# PIC32.net
KiCad netlist of a schematic drawn in Altium Designer
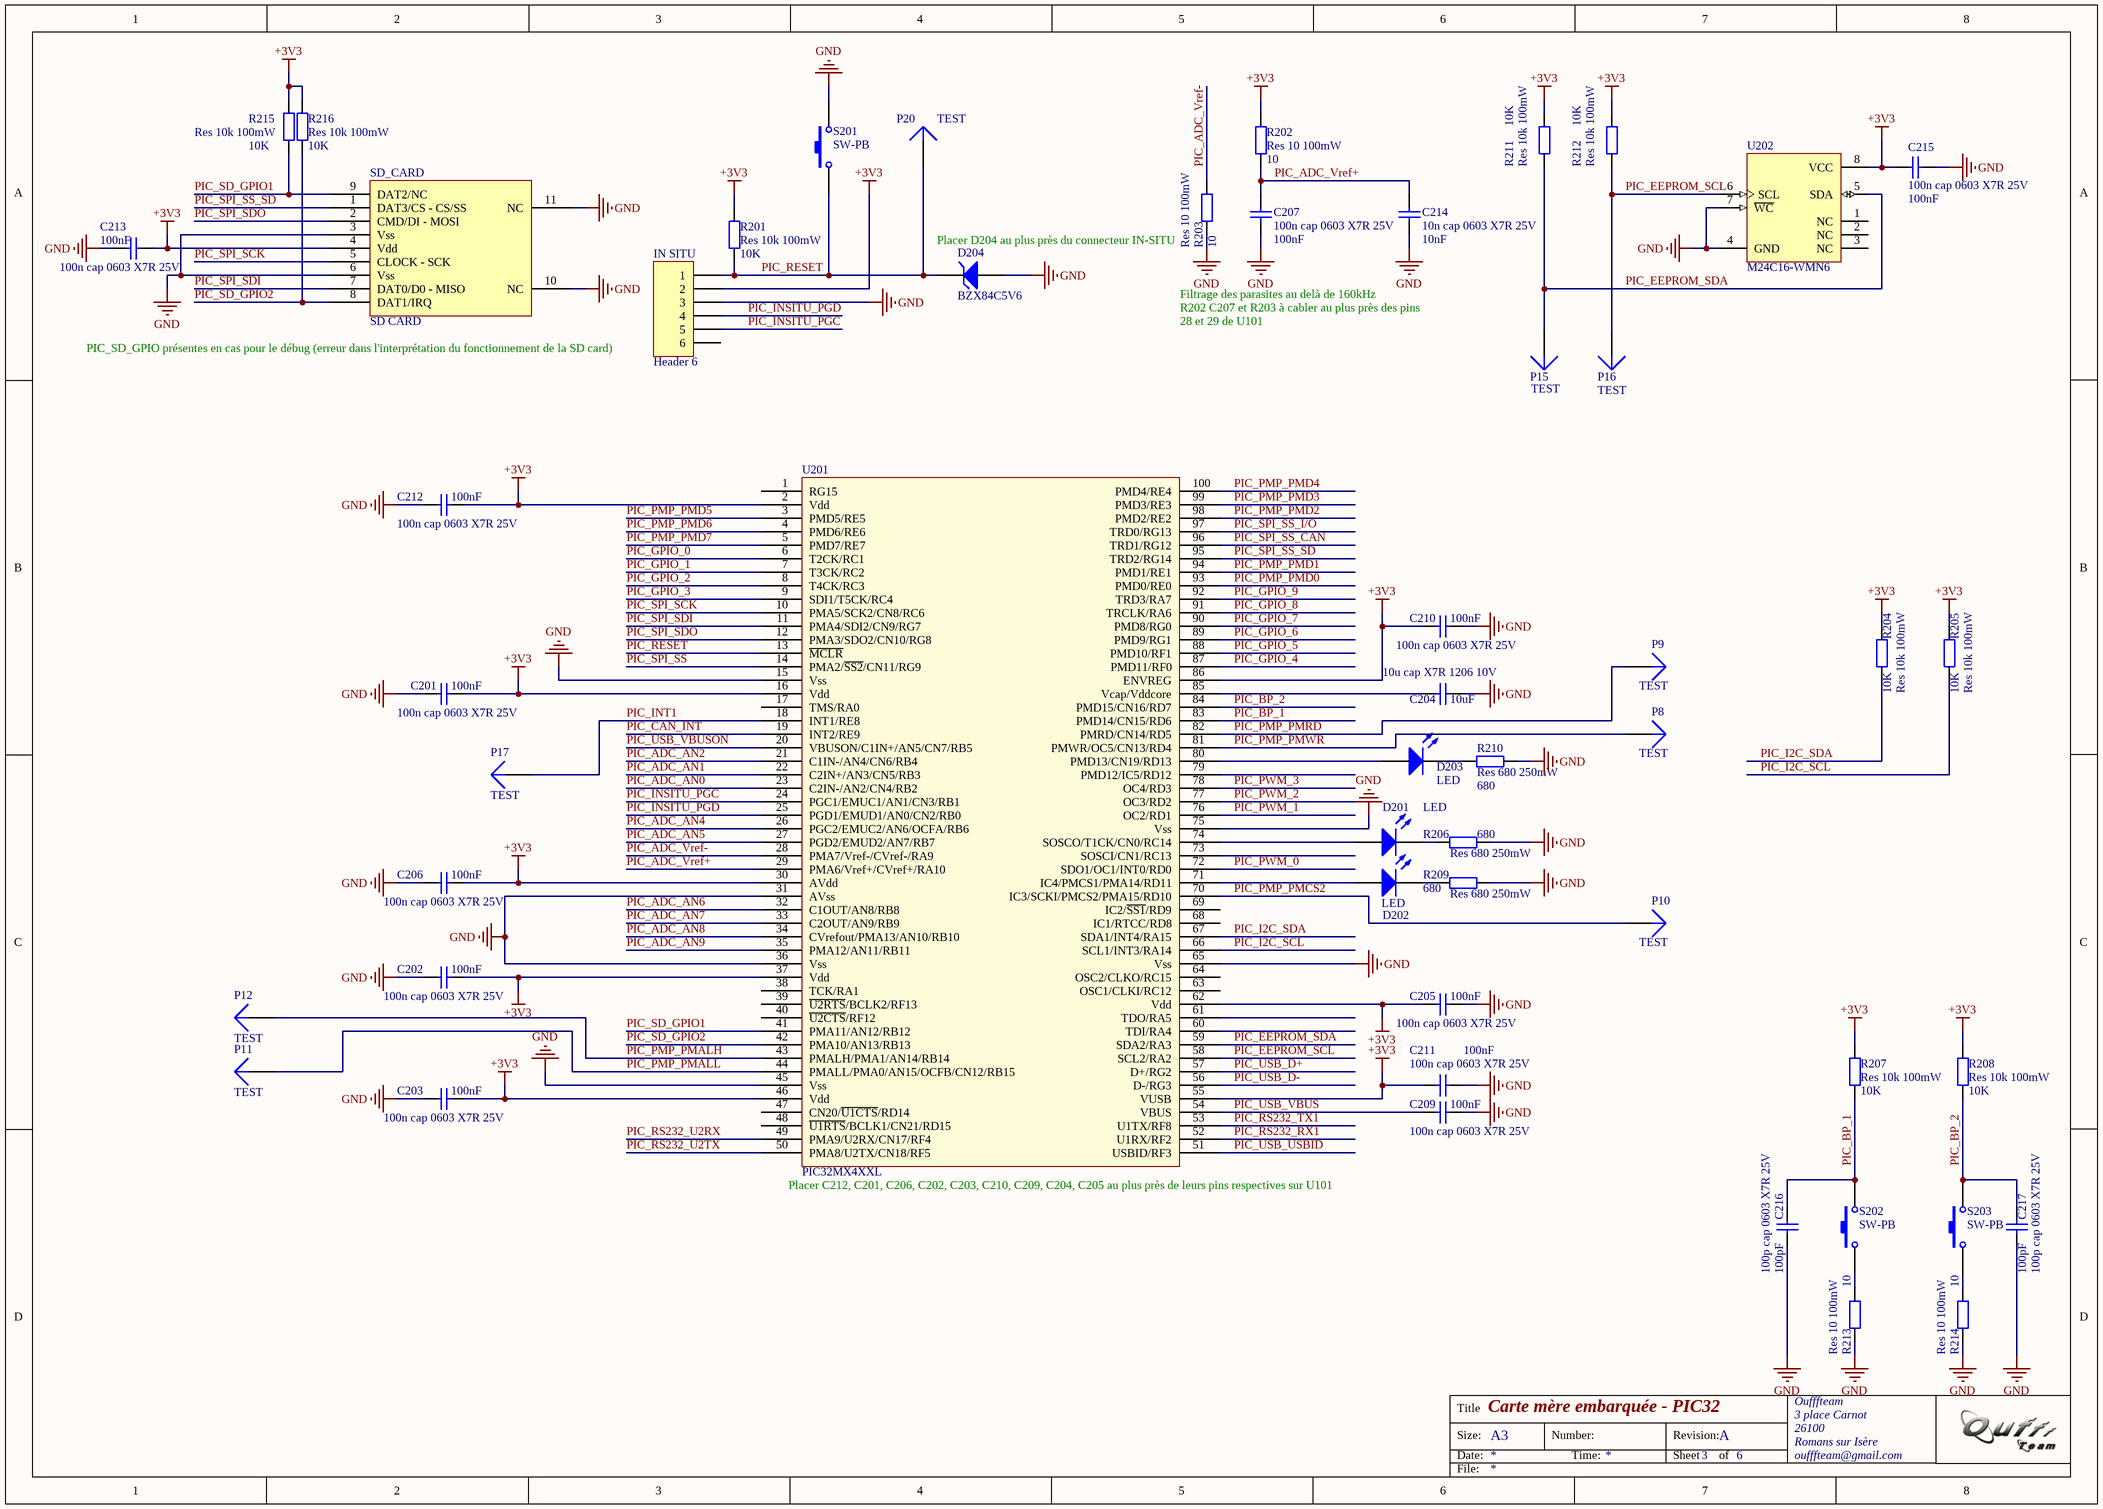
[diagram p0: PIC32.SchDoc]

(export (version "E")
  (design (tool "Eeschema 10.0.6"))
  (components
    (comp (ref "C201")
      (value "100n cap 0603 X7R 25V")
      (footprint "1608[0603]")
      (description "Capacitor")
      (fields (field (name "ALTIUM_VALUE") "100nF") (field (name "PUBLISHER") "Altium Limited"))
      (libsource (lib "Miscellaneous Devices") (part "Cap"))
    )
    (comp (ref "C202")
      (value "100n cap 0603 X7R 25V")
      (footprint "1608[0603]")
      (description "Capacitor")
      (fields (field (name "ALTIUM_VALUE") "100nF") (field (name "PUBLISHER") "Altium Limited"))
      (libsource (lib "Miscellaneous Devices") (part "Cap"))
    )
    (comp (ref "C203")
      (value "100n cap 0603 X7R 25V")
      (footprint "1608[0603]")
      (description "Capacitor")
      (fields (field (name "ALTIUM_VALUE") "100nF") (field (name "PUBLISHER") "Altium Limited"))
      (libsource (lib "Miscellaneous Devices") (part "Cap"))
    )
    (comp (ref "C204")
      (value "10u cap X7R 1206 10V")
      (footprint "3216[1206]")
      (description "Capacitor")
      (fields (field (name "ALTIUM_VALUE") "10uF") (field (name "PUBLISHER") "Altium Limited"))
      (libsource (lib "Miscellaneous Devices") (part "Cap"))
    )
    (comp (ref "C205")
      (value "100n cap 0603 X7R 25V")
      (footprint "1608[0603]")
      (description "Capacitor")
      (fields (field (name "ALTIUM_VALUE") "100nF") (field (name "PUBLISHER") "Altium Limited"))
      (libsource (lib "Miscellaneous Devices") (part "Cap"))
    )
    (comp (ref "C206")
      (value "100n cap 0603 X7R 25V")
      (footprint "1608[0603]")
      (description "Capacitor")
      (fields (field (name "ALTIUM_VALUE") "100nF") (field (name "PUBLISHER") "Altium Limited"))
      (libsource (lib "Miscellaneous Devices") (part "Cap"))
    )
    (comp (ref "C207")
      (value "100n cap 0603 X7R 25V")
      (footprint "1608[0603]")
      (description "Capacitor")
      (fields (field (name "ALTIUM_VALUE") "100nF") (field (name "PUBLISHER") "Altium Limited"))
      (libsource (lib "Miscellaneous Devices") (part "Cap"))
    )
    (comp (ref "C209")
      (value "100n cap 0603 X7R 25V")
      (footprint "1608[0603]")
      (description "Capacitor")
      (fields (field (name "ALTIUM_VALUE") "100nF") (field (name "PUBLISHER") "Altium Limited"))
      (libsource (lib "Miscellaneous Devices") (part "Cap"))
    )
    (comp (ref "C210")
      (value "100n cap 0603 X7R 25V")
      (footprint "1608[0603]")
      (description "Capacitor")
      (fields (field (name "ALTIUM_VALUE") "100nF") (field (name "PUBLISHER") "Altium Limited"))
      (libsource (lib "Miscellaneous Devices") (part "Cap"))
    )
    (comp (ref "C211")
      (value "100n cap 0603 X7R 25V")
      (footprint "1608[0603]")
      (description "Capacitor")
      (fields (field (name "ALTIUM_VALUE") "100nF") (field (name "PUBLISHER") "Altium Limited"))
      (libsource (lib "Miscellaneous Devices") (part "Cap"))
    )
    (comp (ref "C212")
      (value "100n cap 0603 X7R 25V")
      (footprint "1608[0603]")
      (description "Capacitor")
      (fields (field (name "ALTIUM_VALUE") "100nF") (field (name "PUBLISHER") "Altium Limited"))
      (libsource (lib "Miscellaneous Devices") (part "Cap"))
    )
    (comp (ref "C213")
      (value "100n cap 0603 X7R 25V")
      (footprint "1608[0603]")
      (description "Capacitor")
      (fields (field (name "ALTIUM_VALUE") "100nF") (field (name "PUBLISHER") "Altium Limited"))
      (libsource (lib "Miscellaneous Devices") (part "Cap"))
    )
    (comp (ref "C214")
      (value "10n cap 0603 X7R 25V")
      (footprint "1608[0603]")
      (description "Capacitor")
      (fields (field (name "ALTIUM_VALUE") "10nF") (field (name "PUBLISHER") "Altium Limited"))
      (libsource (lib "Miscellaneous Devices") (part "Cap"))
    )
    (comp (ref "C215")
      (value "100n cap 0603 X7R 25V")
      (footprint "1608[0603]")
      (description "Capacitor")
      (fields (field (name "ALTIUM_VALUE") "100nF") (field (name "PUBLISHER") "Altium Limited"))
      (libsource (lib "Miscellaneous Devices") (part "Cap"))
    )
    (comp (ref "C216")
      (value "100p cap 0603 X7R 25V")
      (footprint "1608[0603]")
      (description "Capacitor")
      (fields (field (name "ALTIUM_VALUE") "100pF") (field (name "PUBLISHER") "Altium Limited"))
      (libsource (lib "Miscellaneous Devices") (part "Cap"))
    )
    (comp (ref "C217")
      (value "100p cap 0603 X7R 25V")
      (footprint "1608[0603]")
      (description "Capacitor")
      (fields (field (name "ALTIUM_VALUE") "100pF") (field (name "PUBLISHER") "Altium Limited"))
      (libsource (lib "Miscellaneous Devices") (part "Cap"))
    )
    (comp (ref "D201")
      (value "LED")
      (footprint "1608[0603]")
      (description "LED SML-311DTT86")
      (fields (field (name "PUBLISHER") "Altium Limited"))
      (libsource (lib "Miscellaneous Devices") (part "LED0"))
    )
    (comp (ref "D202")
      (value "LED")
      (footprint "1608[0603]")
      (description "LED SML-311DTT86")
      (fields (field (name "PUBLISHER") "Altium Limited"))
      (libsource (lib "Miscellaneous Devices") (part "LED0"))
    )
    (comp (ref "D203")
      (value "LED")
      (footprint "1608[0603]")
      (description "LED SML-311DTT86")
      (fields (field (name "PUBLISHER") "Altium Limited"))
      (libsource (lib "Miscellaneous Devices") (part "LED0"))
    )
    (comp (ref "D204")
      (value "BZX84C5V6")
      (footprint "318-07")
      (description "Zener Voltage Regulator Diode")
      (fields (field (name "PUBLISHER") "Altium Limited"))
      (libsource (lib "Motorola Discrete Diode") (part "BZX84C5V6LT1"))
    )
    (comp (ref "IN SITU")
      (value "Header 6")
      (footprint "HDR1X6")
      (description "Header, 6-Pin")
      (fields (field (name "PUBLISHER") "Altium Limited"))
      (libsource (lib "Miscellaneous Connectors") (part "Header 6"))
    )
    (comp (ref "P8")
      (value "TEST")
      (footprint "TP1")
      (description "Plug")
      (fields (field (name "PUBLISHER") "Altium Limited"))
      (libsource (lib "Miscellaneous Connectors") (part "Plug"))
    )
    (comp (ref "P9")
      (value "TEST")
      (footprint "TP1")
      (description "Plug")
      (fields (field (name "PUBLISHER") "Altium Limited"))
      (libsource (lib "Miscellaneous Connectors") (part "Plug"))
    )
    (comp (ref "P10")
      (value "TEST")
      (footprint "TP1")
      (description "Plug")
      (fields (field (name "PUBLISHER") "Altium Limited"))
      (libsource (lib "Miscellaneous Connectors") (part "Plug"))
    )
    (comp (ref "P11")
      (value "TEST")
      (footprint "TP1")
      (description "Plug")
      (fields (field (name "PUBLISHER") "Altium Limited"))
      (libsource (lib "Miscellaneous Connectors") (part "Plug"))
    )
    (comp (ref "P12")
      (value "TEST")
      (footprint "TP1")
      (description "Plug")
      (fields (field (name "PUBLISHER") "Altium Limited"))
      (libsource (lib "Miscellaneous Connectors") (part "Plug"))
    )
    (comp (ref "P15")
      (value "TEST")
      (footprint "TP1")
      (description "Plug")
      (fields (field (name "PUBLISHER") "Altium Limited"))
      (libsource (lib "Miscellaneous Connectors") (part "Plug"))
    )
    (comp (ref "P16")
      (value "TEST")
      (footprint "TP1")
      (description "Plug")
      (fields (field (name "PUBLISHER") "Altium Limited"))
      (libsource (lib "Miscellaneous Connectors") (part "Plug"))
    )
    (comp (ref "P17")
      (value "TEST")
      (footprint "TP1")
      (description "Plug")
      (fields (field (name "PUBLISHER") "Altium Limited"))
      (libsource (lib "Miscellaneous Connectors") (part "Plug"))
    )
    (comp (ref "P20")
      (value "TEST")
      (footprint "TP1")
      (description "Plug")
      (fields (field (name "PUBLISHER") "Altium Limited"))
      (libsource (lib "Miscellaneous Connectors") (part "Plug"))
    )
    (comp (ref "R201")
      (value "Res 10k 100mW")
      (footprint "1608[0603]")
      (description "Resistor")
      (fields (field (name "ALTIUM_VALUE") "10K") (field (name "PUBLISHER") "Altium Limited"))
      (libsource (lib "Miscellaneous Devices") (part "Res2"))
    )
    (comp (ref "R202")
      (value "Res 10 100mW")
      (footprint "1608[0603]")
      (description "Resistor")
      (fields (field (name "ALTIUM_VALUE") "10") (field (name "PUBLISHER") "Altium Limited"))
      (libsource (lib "Miscellaneous Devices") (part "Res2"))
    )
    (comp (ref "R203")
      (value "Res 10 100mW")
      (footprint "1608[0603]")
      (description "Resistor")
      (fields (field (name "ALTIUM_VALUE") "10") (field (name "PUBLISHER") "Altium Limited"))
      (libsource (lib "Miscellaneous Devices") (part "Res2"))
    )
    (comp (ref "R204")
      (value "Res 10k 100mW")
      (footprint "1608[0603]")
      (description "Resistor")
      (fields (field (name "ALTIUM_VALUE") "10K") (field (name "PUBLISHER") "Altium Limited"))
      (libsource (lib "Miscellaneous Devices") (part "Res2"))
    )
    (comp (ref "R205")
      (value "Res 10k 100mW")
      (footprint "1608[0603]")
      (description "Resistor")
      (fields (field (name "ALTIUM_VALUE") "10K") (field (name "PUBLISHER") "Altium Limited"))
      (libsource (lib "Miscellaneous Devices") (part "Res2"))
    )
    (comp (ref "R206")
      (value "Res 680 250mW")
      (footprint "1608[0603]")
      (description "Resistor")
      (fields (field (name "ALTIUM_VALUE") "680") (field (name "PUBLISHER") "Altium Limited"))
      (libsource (lib "") (part "Res2_1"))
    )
    (comp (ref "R207")
      (value "Res 10k 100mW")
      (footprint "1608[0603]")
      (description "Resistor")
      (fields (field (name "ALTIUM_VALUE") "10K") (field (name "PUBLISHER") "Altium Limited"))
      (libsource (lib "Miscellaneous Devices") (part "Res2"))
    )
    (comp (ref "R208")
      (value "Res 10k 100mW")
      (footprint "1608[0603]")
      (description "Resistor")
      (fields (field (name "ALTIUM_VALUE") "10K") (field (name "PUBLISHER") "Altium Limited"))
      (libsource (lib "Miscellaneous Devices") (part "Res2"))
    )
    (comp (ref "R209")
      (value "Res 680 250mW")
      (footprint "1608[0603]")
      (description "Resistor")
      (fields (field (name "ALTIUM_VALUE") "680") (field (name "PUBLISHER") "Altium Limited"))
      (libsource (lib "") (part "Res2_1"))
    )
    (comp (ref "R210")
      (value "Res 680 250mW")
      (footprint "1608[0603]")
      (description "Resistor")
      (fields (field (name "ALTIUM_VALUE") "680") (field (name "PUBLISHER") "Altium Limited"))
      (libsource (lib "") (part "Res2_1"))
    )
    (comp (ref "R211")
      (value "Res 10k 100mW")
      (footprint "1608[0603]")
      (description "Resistor")
      (fields (field (name "ALTIUM_VALUE") "10K") (field (name "PUBLISHER") "Altium Limited"))
      (libsource (lib "Miscellaneous Devices") (part "Res2"))
    )
    (comp (ref "R212")
      (value "Res 10k 100mW")
      (footprint "1608[0603]")
      (description "Resistor")
      (fields (field (name "ALTIUM_VALUE") "10K") (field (name "PUBLISHER") "Altium Limited"))
      (libsource (lib "Miscellaneous Devices") (part "Res2"))
    )
    (comp (ref "R213")
      (value "Res 10 100mW")
      (footprint "1608[0603]")
      (description "Resistor")
      (fields (field (name "ALTIUM_VALUE") "10") (field (name "PUBLISHER") "Altium Limited"))
      (libsource (lib "Miscellaneous Devices") (part "Res2"))
    )
    (comp (ref "R214")
      (value "Res 10 100mW")
      (footprint "1608[0603]")
      (description "Resistor")
      (fields (field (name "ALTIUM_VALUE") "10") (field (name "PUBLISHER") "Altium Limited"))
      (libsource (lib "Miscellaneous Devices") (part "Res2"))
    )
    (comp (ref "R215")
      (value "Res 10k 100mW")
      (footprint "1608[0603]")
      (description "Resistor")
      (fields (field (name "ALTIUM_VALUE") "10K") (field (name "PUBLISHER") "Altium Limited"))
      (libsource (lib "Miscellaneous Devices") (part "Res2"))
    )
    (comp (ref "R216")
      (value "Res 10k 100mW")
      (footprint "1608[0603]")
      (description "Resistor")
      (fields (field (name "ALTIUM_VALUE") "10K") (field (name "PUBLISHER") "Altium Limited"))
      (libsource (lib "Miscellaneous Devices") (part "Res2"))
    )
    (comp (ref "S201")
      (value "SW-PB")
      (footprint "BP1")
      (description "Switch")
      (fields (field (name "PUBLISHER") "Altium Limited"))
      (libsource (lib "Miscellaneous Devices") (part "SW-PB"))
    )
    (comp (ref "S202")
      (value "SW-PB")
      (footprint "BP1")
      (description "Switch")
      (fields (field (name "PUBLISHER") "Altium Limited"))
      (libsource (lib "Miscellaneous Devices") (part "SW-PB"))
    )
    (comp (ref "S203")
      (value "SW-PB")
      (footprint "BP1")
      (description "Switch")
      (fields (field (name "PUBLISHER") "Altium Limited"))
      (libsource (lib "Miscellaneous Devices") (part "SW-PB"))
    )
    (comp (ref "SD_CARD")
      (value "SD CARD")
      (footprint "SDHolder")
      (description "SD Card Holder")
      (libsource (lib "Oufff_Lib") (part "SD CARD"))
    )
    (comp (ref "U201")
      (value "PIC32MX4XXL")
      (footprint "TSQFP40P1400X1400X120-100N")
      (description "PIC32")
      (libsource (lib "Oufff_Lib") (part "PIC32MX4XXL"))
    )
    (comp (ref "U202")
      (value "M24C16-WMN6")
      (footprint "SOP8_N")
      (description "16Kbit Serial I²C Bus EEPROM")
      (fields (field (name "PUBLISHER") "Altium Limited"))
      (libsource (lib "ST Memory EEPROM Serial") (part "M24C16MN6"))
    )
  )
  (nets
    (net (code "1") (name "+3V3") (class "Default")
      (node (ref "C201") (pin "2") (pinfunction "2_2") (pintype "passive"))
      (node (ref "C202") (pin "2") (pinfunction "2_2") (pintype "passive"))
      (node (ref "C203") (pin "2") (pinfunction "2_2") (pintype "passive"))
      (node (ref "C205") (pin "1") (pinfunction "1_1") (pintype "passive"))
      (node (ref "C206") (pin "2") (pinfunction "2_2") (pintype "passive"))
      (node (ref "C210") (pin "1") (pinfunction "1_1") (pintype "passive"))
      (node (ref "C211") (pin "1") (pinfunction "1_1") (pintype "passive"))
      (node (ref "C212") (pin "2") (pinfunction "2_2") (pintype "passive"))
      (node (ref "C213") (pin "2") (pinfunction "2_2") (pintype "passive"))
      (node (ref "C215") (pin "1") (pinfunction "1_1") (pintype "passive"))
      (node (ref "IN SITU") (pin "2") (pinfunction "2_2") (pintype "passive"))
      (node (ref "R201") (pin "2") (pinfunction "2_2") (pintype "passive"))
      (node (ref "R202") (pin "2") (pinfunction "2_2") (pintype "passive"))
      (node (ref "R204") (pin "2") (pinfunction "2_2") (pintype "passive"))
      (node (ref "R205") (pin "2") (pinfunction "2_2") (pintype "passive"))
      (node (ref "R207") (pin "2") (pinfunction "2_2") (pintype "passive"))
      (node (ref "R208") (pin "2") (pinfunction "2_2") (pintype "passive"))
      (node (ref "R211") (pin "2") (pinfunction "2_2") (pintype "passive"))
      (node (ref "R212") (pin "2") (pinfunction "2_2") (pintype "passive"))
      (node (ref "R215") (pin "2") (pinfunction "2_2") (pintype "passive"))
      (node (ref "R216") (pin "2") (pinfunction "2_2") (pintype "passive"))
      (node (ref "SD_CARD") (pin "4") (pinfunction "Vdd_4") (pintype "passive"))
      (node (ref "U201") (pin "16") (pinfunction "Vdd_16") (pintype "passive"))
      (node (ref "U201") (pin "2") (pinfunction "Vdd_2") (pintype "passive"))
      (node (ref "U201") (pin "30") (pinfunction "AVdd_30") (pintype "passive"))
      (node (ref "U201") (pin "37") (pinfunction "Vdd_37") (pintype "passive"))
      (node (ref "U201") (pin "46") (pinfunction "Vdd_46") (pintype "passive"))
      (node (ref "U201") (pin "55") (pinfunction "VUSB_55") (pintype "passive"))
      (node (ref "U201") (pin "62") (pinfunction "Vdd_62") (pintype "passive"))
      (node (ref "U201") (pin "86") (pinfunction "ENVREG_86") (pintype "passive"))
      (node (ref "U202") (pin "8") (pinfunction "VCC_8") (pintype "power_in"))
    )
    (net (code "2") (name "/PIC_ADC_AN0") (class "Default")
      (node (ref "U201") (pin "23") (pinfunction "C2IN-/AN2/CN4/RB2_23") (pintype "passive"))
    )
    (net (code "3") (name "/PIC_ADC_AN1") (class "Default")
      (node (ref "U201") (pin "22") (pinfunction "C2IN+/AN3/CN5/RB3_22") (pintype "passive"))
    )
    (net (code "4") (name "/PIC_ADC_AN2") (class "Default")
      (node (ref "U201") (pin "21") (pinfunction "C1IN-/AN4/CN6/RB4_21") (pintype "passive"))
    )
    (net (code "5") (name "/PIC_ADC_AN4") (class "Default")
      (node (ref "U201") (pin "26") (pinfunction "PGC2/EMUC2/AN6/OCFA/RB6_26") (pintype "passive"))
    )
    (net (code "6") (name "/PIC_ADC_AN5") (class "Default")
      (node (ref "U201") (pin "27") (pinfunction "PGD2/EMUD2/AN7/RB7_27") (pintype "passive"))
    )
    (net (code "7") (name "/PIC_ADC_AN6") (class "Default")
      (node (ref "U201") (pin "32") (pinfunction "C1OUT/AN8/RB8_32") (pintype "passive"))
    )
    (net (code "8") (name "/PIC_ADC_AN7") (class "Default")
      (node (ref "U201") (pin "33") (pinfunction "C2OUT/AN9/RB9_33") (pintype "passive"))
    )
    (net (code "9") (name "/PIC_ADC_AN8") (class "Default")
      (node (ref "U201") (pin "34") (pinfunction "CVrefout/PMA13/AN10/RB10_34") (pintype "passive"))
    )
    (net (code "10") (name "/PIC_ADC_AN9") (class "Default")
      (node (ref "U201") (pin "35") (pinfunction "PMA12/AN11/RB11_35") (pintype "passive"))
    )
    (net (code "11") (name "/PIC_ADC_Vref+") (class "Default")
      (node (ref "C207") (pin "2") (pinfunction "2_2") (pintype "passive"))
      (node (ref "C214") (pin "2") (pinfunction "2_2") (pintype "passive"))
      (node (ref "R202") (pin "1") (pinfunction "1_1") (pintype "passive"))
      (node (ref "U201") (pin "29") (pinfunction "PMA6/Vref+/CVref+/RA10_29") (pintype "passive"))
    )
    (net (code "12") (name "/PIC_ADC_Vref-") (class "Default")
      (node (ref "R203") (pin "2") (pinfunction "2_2") (pintype "passive"))
      (node (ref "U201") (pin "28") (pinfunction "PMA7/Vref-/CVref-/RA9_28") (pintype "passive"))
    )
    (net (code "13") (name "/PIC_BP_1") (class "Default")
      (node (ref "C216") (pin "2") (pinfunction "2_2") (pintype "passive"))
      (node (ref "R207") (pin "1") (pinfunction "1_1") (pintype "passive"))
      (node (ref "S202") (pin "3") (pinfunction "3_3") (pintype "passive"))
      (node (ref "U201") (pin "83") (pinfunction "PMD14/CN15/RD6_83") (pintype "passive"))
    )
    (net (code "14") (name "/PIC_BP_2") (class "Default")
      (node (ref "C217") (pin "2") (pinfunction "2_2") (pintype "passive"))
      (node (ref "R208") (pin "1") (pinfunction "1_1") (pintype "passive"))
      (node (ref "S203") (pin "3") (pinfunction "3_3") (pintype "passive"))
      (node (ref "U201") (pin "84") (pinfunction "PMD15/CN16/RD7_84") (pintype "passive"))
    )
    (net (code "15") (name "/PIC_CAN_INT") (class "Default")
      (node (ref "U201") (pin "19") (pinfunction "INT2/RE9_19") (pintype "passive"))
    )
    (net (code "16") (name "/PIC_EEPROM_SCL") (class "Default")
      (node (ref "P16") (pin "1") (pinfunction "1_1") (pintype "passive"))
      (node (ref "R212") (pin "1") (pinfunction "1_1") (pintype "passive"))
      (node (ref "U201") (pin "58") (pinfunction "SCL2/RA2_58") (pintype "passive"))
      (node (ref "U202") (pin "6") (pinfunction "SCL_6") (pintype "input"))
    )
    (net (code "17") (name "/PIC_EEPROM_SDA") (class "Default")
      (node (ref "P15") (pin "1") (pinfunction "1_1") (pintype "passive"))
      (node (ref "R211") (pin "1") (pinfunction "1_1") (pintype "passive"))
      (node (ref "U201") (pin "59") (pinfunction "SDA2/RA3_59") (pintype "passive"))
      (node (ref "U202") (pin "5") (pinfunction "SDA_5") (pintype "bidirectional"))
    )
    (net (code "18") (name "/PIC_GPIO_0") (class "Default")
      (node (ref "U201") (pin "6") (pinfunction "T2CK/RC1_6") (pintype "passive"))
    )
    (net (code "19") (name "/PIC_GPIO_1") (class "Default")
      (node (ref "U201") (pin "7") (pinfunction "T3CK/RC2_7") (pintype "passive"))
    )
    (net (code "20") (name "/PIC_GPIO_2") (class "Default")
      (node (ref "U201") (pin "8") (pinfunction "T4CK/RC3_8") (pintype "passive"))
    )
    (net (code "21") (name "/PIC_GPIO_3") (class "Default")
      (node (ref "U201") (pin "9") (pinfunction "SDI1/T5CK/RC4_9") (pintype "passive"))
    )
    (net (code "22") (name "/PIC_GPIO_4") (class "Default")
      (node (ref "U201") (pin "87") (pinfunction "PMD11/RF0_87") (pintype "passive"))
    )
    (net (code "23") (name "/PIC_GPIO_5") (class "Default")
      (node (ref "U201") (pin "88") (pinfunction "PMD10/RF1_88") (pintype "passive"))
    )
    (net (code "24") (name "/PIC_GPIO_6") (class "Default")
      (node (ref "U201") (pin "89") (pinfunction "PMD9/RG1_89") (pintype "passive"))
    )
    (net (code "25") (name "/PIC_GPIO_7") (class "Default")
      (node (ref "U201") (pin "90") (pinfunction "PMD8/RG0_90") (pintype "passive"))
    )
    (net (code "26") (name "/PIC_GPIO_8") (class "Default")
      (node (ref "U201") (pin "91") (pinfunction "TRCLK/RA6_91") (pintype "passive"))
    )
    (net (code "27") (name "/PIC_GPIO_9") (class "Default")
      (node (ref "U201") (pin "92") (pinfunction "TRD3/RA7_92") (pintype "passive"))
    )
    (net (code "28") (name "/PIC_I2C_SCL") (class "Default")
      (node (ref "R205") (pin "1") (pinfunction "1_1") (pintype "passive"))
      (node (ref "U201") (pin "66") (pinfunction "SCL1/INT3/RA14_66") (pintype "passive"))
    )
    (net (code "29") (name "/PIC_I2C_SDA") (class "Default")
      (node (ref "R204") (pin "1") (pinfunction "1_1") (pintype "passive"))
      (node (ref "U201") (pin "67") (pinfunction "SDA1/INT4/RA15_67") (pintype "passive"))
    )
    (net (code "30") (name "/PIC_INSITU_PGC") (class "Default")
      (node (ref "IN SITU") (pin "5") (pinfunction "5_5") (pintype "passive"))
      (node (ref "U201") (pin "24") (pinfunction "PGC1/EMUC1/AN1/CN3/RB1_24") (pintype "passive"))
    )
    (net (code "31") (name "/PIC_INSITU_PGD") (class "Default")
      (node (ref "IN SITU") (pin "4") (pinfunction "4_4") (pintype "passive"))
      (node (ref "U201") (pin "25") (pinfunction "PGD1/EMUD1/AN0/CN2/RB0_25") (pintype "passive"))
    )
    (net (code "32") (name "/PIC_INT1") (class "Default")
      (node (ref "P17") (pin "1") (pinfunction "1_1") (pintype "passive"))
      (node (ref "U201") (pin "18") (pinfunction "INT1/RE8_18") (pintype "passive"))
    )
    (net (code "33") (name "/PIC_PMP_PMALH") (class "Default")
      (node (ref "P12") (pin "1") (pinfunction "1_1") (pintype "passive"))
      (node (ref "U201") (pin "43") (pinfunction "PMALH/PMA1/AN14/RB14_43") (pintype "passive"))
    )
    (net (code "34") (name "/PIC_PMP_PMALL") (class "Default")
      (node (ref "P11") (pin "1") (pinfunction "1_1") (pintype "passive"))
      (node (ref "U201") (pin "44") (pinfunction "PMALL/PMA0/AN15/OCFB/CN12/RB15_44") (pintype "passive"))
    )
    (net (code "35") (name "/PIC_PMP_PMCS2") (class "Default")
      (node (ref "P10") (pin "1") (pinfunction "1_1") (pintype "passive"))
      (node (ref "U201") (pin "70") (pinfunction "IC3/SCKI/PMCS2/PMA15/RD10_70") (pintype "passive"))
    )
    (net (code "36") (name "/PIC_PMP_PMD0") (class "Default")
      (node (ref "U201") (pin "93") (pinfunction "PMD0/RE0_93") (pintype "passive"))
    )
    (net (code "37") (name "/PIC_PMP_PMD1") (class "Default")
      (node (ref "U201") (pin "94") (pinfunction "PMD1/RE1_94") (pintype "passive"))
    )
    (net (code "38") (name "/PIC_PMP_PMD2") (class "Default")
      (node (ref "U201") (pin "98") (pinfunction "PMD2/RE2_98") (pintype "passive"))
    )
    (net (code "39") (name "/PIC_PMP_PMD3") (class "Default")
      (node (ref "U201") (pin "99") (pinfunction "PMD3/RE3_99") (pintype "passive"))
    )
    (net (code "40") (name "/PIC_PMP_PMD4") (class "Default")
      (node (ref "U201") (pin "100") (pinfunction "PMD4/RE4_100") (pintype "passive"))
    )
    (net (code "41") (name "/PIC_PMP_PMD5") (class "Default")
      (node (ref "U201") (pin "3") (pinfunction "PMD5/RE5_3") (pintype "passive"))
    )
    (net (code "42") (name "/PIC_PMP_PMD6") (class "Default")
      (node (ref "U201") (pin "4") (pinfunction "PMD6/RE6_4") (pintype "passive"))
    )
    (net (code "43") (name "/PIC_PMP_PMD7") (class "Default")
      (node (ref "U201") (pin "5") (pinfunction "PMD7/RE7_5") (pintype "passive"))
    )
    (net (code "44") (name "/PIC_PMP_PMRD") (class "Default")
      (node (ref "P9") (pin "1") (pinfunction "1_1") (pintype "passive"))
      (node (ref "U201") (pin "82") (pinfunction "PMRD/CN14/RD5_82") (pintype "passive"))
    )
    (net (code "45") (name "/PIC_PMP_PMWR") (class "Default")
      (node (ref "P8") (pin "1") (pinfunction "1_1") (pintype "passive"))
      (node (ref "U201") (pin "81") (pinfunction "PMWR/OC5/CN13/RD4_81") (pintype "passive"))
    )
    (net (code "46") (name "/PIC_PWM_0") (class "Default")
      (node (ref "U201") (pin "72") (pinfunction "SDO1/OC1/INT0/RD0_72") (pintype "passive"))
    )
    (net (code "47") (name "/PIC_PWM_1") (class "Default")
      (node (ref "U201") (pin "76") (pinfunction "OC2/RD1_76") (pintype "passive"))
    )
    (net (code "48") (name "/PIC_PWM_2") (class "Default")
      (node (ref "U201") (pin "77") (pinfunction "OC3/RD2_77") (pintype "passive"))
    )
    (net (code "49") (name "/PIC_PWM_3") (class "Default")
      (node (ref "U201") (pin "78") (pinfunction "OC4/RD3_78") (pintype "passive"))
    )
    (net (code "50") (name "/PIC_RESET") (class "Default")
      (node (ref "D204") (pin "3") (pinfunction "K_3") (pintype "passive"))
      (node (ref "IN SITU") (pin "1") (pinfunction "1_1") (pintype "passive"))
      (node (ref "P20") (pin "1") (pinfunction "1_1") (pintype "passive"))
      (node (ref "R201") (pin "1") (pinfunction "1_1") (pintype "passive"))
      (node (ref "S201") (pin "1") (pinfunction "1_1") (pintype "passive"))
      (node (ref "U201") (pin "13") (pinfunction "~{MCLR}_13") (pintype "passive"))
    )
    (net (code "51") (name "/PIC_RS232_RX1") (class "Default")
      (node (ref "U201") (pin "52") (pinfunction "U1RX/RF2_52") (pintype "passive"))
    )
    (net (code "52") (name "/PIC_RS232_TX1") (class "Default")
      (node (ref "U201") (pin "53") (pinfunction "U1TX/RF8_53") (pintype "passive"))
    )
    (net (code "53") (name "/PIC_RS232_U2RX") (class "Default")
      (node (ref "U201") (pin "49") (pinfunction "PMA9/U2RX/CN17/RF4_49") (pintype "passive"))
    )
    (net (code "54") (name "/PIC_RS232_U2TX") (class "Default")
      (node (ref "U201") (pin "50") (pinfunction "PMA8/U2TX/CN18/RF5_50") (pintype "passive"))
    )
    (net (code "55") (name "/PIC_SD_GPIO1") (class "Default")
      (node (ref "R215") (pin "1") (pinfunction "1_1") (pintype "passive"))
      (node (ref "SD_CARD") (pin "9") (pinfunction "DAT2/NC_9") (pintype "passive"))
      (node (ref "U201") (pin "41") (pinfunction "PMA11/AN12/RB12_41") (pintype "passive"))
    )
    (net (code "56") (name "/PIC_SD_GPIO2") (class "Default")
      (node (ref "R216") (pin "1") (pinfunction "1_1") (pintype "passive"))
      (node (ref "SD_CARD") (pin "8") (pinfunction "DAT1/IRQ_8") (pintype "passive"))
      (node (ref "U201") (pin "42") (pinfunction "PMA10/AN13/RB13_42") (pintype "passive"))
    )
    (net (code "57") (name "/PIC_SPI_SCK") (class "Default")
      (node (ref "SD_CARD") (pin "5") (pinfunction "CLOCK_-_SCK_5") (pintype "passive"))
      (node (ref "U201") (pin "10") (pinfunction "PMA5/SCK2/CN8/RC6_10") (pintype "passive"))
    )
    (net (code "58") (name "/PIC_SPI_SDI") (class "Default")
      (node (ref "SD_CARD") (pin "7") (pinfunction "DAT0/D0_-_MISO_7") (pintype "passive"))
      (node (ref "U201") (pin "11") (pinfunction "PMA4/SDI2/CN9/RG7_11") (pintype "passive"))
    )
    (net (code "59") (name "/PIC_SPI_SDO") (class "Default")
      (node (ref "SD_CARD") (pin "2") (pinfunction "CMD/DI_-_MOSI_2") (pintype "passive"))
      (node (ref "U201") (pin "12") (pinfunction "PMA3/SDO2/CN10/RG8_12") (pintype "passive"))
    )
    (net (code "60") (name "/PIC_SPI_SS") (class "Default")
      (node (ref "U201") (pin "14") (pinfunction "PMA2/~{SS2}/CN11/RG9_14") (pintype "passive"))
    )
    (net (code "61") (name "/PIC_SPI_SS_CAN") (class "Default")
      (node (ref "U201") (pin "96") (pinfunction "TRD1/RG12_96") (pintype "passive"))
    )
    (net (code "62") (name "/PIC_SPI_SS_I{slash}O") (class "Default")
      (node (ref "U201") (pin "97") (pinfunction "TRD0/RG13_97") (pintype "passive"))
    )
    (net (code "63") (name "/PIC_SPI_SS_SD") (class "Default")
      (node (ref "SD_CARD") (pin "1") (pinfunction "DAT3/CS_-_CS/SS_1") (pintype "passive"))
      (node (ref "U201") (pin "95") (pinfunction "TRD2/RG14_95") (pintype "passive"))
    )
    (net (code "64") (name "/PIC_USB_D+") (class "Default")
      (node (ref "U201") (pin "57") (pinfunction "D+/RG2_57") (pintype "passive"))
    )
    (net (code "65") (name "/PIC_USB_D-") (class "Default")
      (node (ref "U201") (pin "56") (pinfunction "D-/RG3_56") (pintype "passive"))
    )
    (net (code "66") (name "/PIC_USB_USBID") (class "Default")
      (node (ref "U201") (pin "51") (pinfunction "USBID/RF3_51") (pintype "passive"))
    )
    (net (code "67") (name "/PIC_USB_VBUS") (class "Default")
      (node (ref "C209") (pin "1") (pinfunction "1_1") (pintype "passive"))
      (node (ref "U201") (pin "54") (pinfunction "VBUS_54") (pintype "passive"))
    )
    (net (code "68") (name "/PIC_USB_VBUSON") (class "Default")
      (node (ref "U201") (pin "20") (pinfunction "VBUSON/C1IN+/AN5/CN7/RB5_20") (pintype "passive"))
    )
    (net (code "69") (name "GND") (class "Default")
      (node (ref "C201") (pin "1") (pinfunction "1_1") (pintype "passive"))
      (node (ref "C202") (pin "1") (pinfunction "1_1") (pintype "passive"))
      (node (ref "C203") (pin "1") (pinfunction "1_1") (pintype "passive"))
      (node (ref "C204") (pin "2") (pinfunction "2_2") (pintype "passive"))
      (node (ref "C205") (pin "2") (pinfunction "2_2") (pintype "passive"))
      (node (ref "C206") (pin "1") (pinfunction "1_1") (pintype "passive"))
      (node (ref "C207") (pin "1") (pinfunction "1_1") (pintype "passive"))
      (node (ref "C209") (pin "2") (pinfunction "2_2") (pintype "passive"))
      (node (ref "C210") (pin "2") (pinfunction "2_2") (pintype "passive"))
      (node (ref "C211") (pin "2") (pinfunction "2_2") (pintype "passive"))
      (node (ref "C212") (pin "1") (pinfunction "1_1") (pintype "passive"))
      (node (ref "C213") (pin "1") (pinfunction "1_1") (pintype "passive"))
      (node (ref "C214") (pin "1") (pinfunction "1_1") (pintype "passive"))
      (node (ref "C215") (pin "2") (pinfunction "2_2") (pintype "passive"))
      (node (ref "C216") (pin "1") (pinfunction "1_1") (pintype "passive"))
      (node (ref "C217") (pin "1") (pinfunction "1_1") (pintype "passive"))
      (node (ref "D204") (pin "1") (pinfunction "A_1") (pintype "passive"))
      (node (ref "IN SITU") (pin "3") (pinfunction "3_3") (pintype "passive"))
      (node (ref "R203") (pin "1") (pinfunction "1_1") (pintype "passive"))
      (node (ref "R206") (pin "2") (pinfunction "2_2") (pintype "passive"))
      (node (ref "R209") (pin "2") (pinfunction "2_2") (pintype "passive"))
      (node (ref "R210") (pin "2") (pinfunction "2_2") (pintype "passive"))
      (node (ref "R213") (pin "1") (pinfunction "1_1") (pintype "passive"))
      (node (ref "R214") (pin "1") (pinfunction "1_1") (pintype "passive"))
      (node (ref "S201") (pin "3") (pinfunction "3_3") (pintype "passive"))
      (node (ref "SD_CARD") (pin "10") (pinfunction "NC_10") (pintype "passive"))
      (node (ref "SD_CARD") (pin "11") (pinfunction "NC_11") (pintype "passive"))
      (node (ref "SD_CARD") (pin "3") (pinfunction "Vss_3") (pintype "passive"))
      (node (ref "SD_CARD") (pin "6") (pinfunction "Vss_6") (pintype "passive"))
      (node (ref "U201") (pin "15") (pinfunction "Vss_15") (pintype "passive"))
      (node (ref "U201") (pin "31") (pinfunction "AVss_31") (pintype "passive"))
      (node (ref "U201") (pin "36") (pinfunction "Vss_36") (pintype "passive"))
      (node (ref "U201") (pin "45") (pinfunction "Vss_45") (pintype "passive"))
      (node (ref "U201") (pin "65") (pinfunction "Vss_65") (pintype "passive"))
      (node (ref "U201") (pin "75") (pinfunction "Vss_75") (pintype "passive"))
      (node (ref "U202") (pin "4") (pinfunction "GND_4") (pintype "power_in"))
      (node (ref "U202") (pin "7") (pinfunction "~{WC}_7") (pintype "input"))
    )
    (net (code "70") (name "Net-(D201-A)") (class "Default")
      (node (ref "D201") (pin "1") (pinfunction "A_1") (pintype "passive"))
      (node (ref "U201") (pin "74") (pinfunction "SOSCO/T1CK/CN0/RC14_74") (pintype "passive"))
    )
    (net (code "71") (name "Net-(D201-K)") (class "Default")
      (node (ref "D201") (pin "2") (pinfunction "K_2") (pintype "passive"))
      (node (ref "R206") (pin "1") (pinfunction "1_1") (pintype "passive"))
    )
    (net (code "72") (name "Net-(D202-A)") (class "Default")
      (node (ref "D202") (pin "1") (pinfunction "A_1") (pintype "passive"))
      (node (ref "U201") (pin "71") (pinfunction "IC4/PMCS1/PMA14/RD11_71") (pintype "passive"))
    )
    (net (code "73") (name "Net-(D202-K)") (class "Default")
      (node (ref "D202") (pin "2") (pinfunction "K_2") (pintype "passive"))
      (node (ref "R209") (pin "1") (pinfunction "1_1") (pintype "passive"))
    )
    (net (code "74") (name "Net-(D203-A)") (class "Default")
      (node (ref "D203") (pin "1") (pinfunction "A_1") (pintype "passive"))
      (node (ref "U201") (pin "80") (pinfunction "PMD13/CN19/RD13_80") (pintype "passive"))
    )
    (net (code "75") (name "Net-(D203-K)") (class "Default")
      (node (ref "D203") (pin "2") (pinfunction "K_2") (pintype "passive"))
      (node (ref "R210") (pin "1") (pinfunction "1_1") (pintype "passive"))
    )
    (net (code "76") (name "Net-(R213-Pad2)") (class "Default")
      (node (ref "R213") (pin "2") (pinfunction "2_2") (pintype "passive"))
      (node (ref "S202") (pin "1") (pinfunction "1_1") (pintype "passive"))
    )
    (net (code "77") (name "Net-(R214-Pad2)") (class "Default")
      (node (ref "R214") (pin "2") (pinfunction "2_2") (pintype "passive"))
      (node (ref "S203") (pin "1") (pinfunction "1_1") (pintype "passive"))
    )
    (net (code "78") (name "Net-(U201-Vcap{slash}Vddcore)") (class "Default")
      (node (ref "C204") (pin "1") (pinfunction "1_1") (pintype "passive"))
      (node (ref "U201") (pin "85") (pinfunction "Vcap/Vddcore_85") (pintype "passive"))
    )
    (net (code "79") (name "unconnected-(IN SITU-Pad6)") (class "Default")
      (node (ref "IN SITU") (pin "6") (pinfunction "6_6") (pintype "passive"))
    )
    (net (code "80") (name "unconnected-(U201-CN20{slash}~{U1CTS}{slash}RD14-Pad47)") (class "Default")
      (node (ref "U201") (pin "47") (pinfunction "CN20/~{U1CTS}/RD14_47") (pintype "passive"))
    )
    (net (code "81") (name "unconnected-(U201-IC1{slash}RTCC{slash}RD8-Pad68)") (class "Default")
      (node (ref "U201") (pin "68") (pinfunction "IC1/RTCC/RD8_68") (pintype "passive"))
    )
    (net (code "82") (name "unconnected-(U201-IC2{slash}~{SS1}{slash}RD9-Pad69)") (class "Default")
      (node (ref "U201") (pin "69") (pinfunction "IC2/~{SS1}/RD9_69") (pintype "passive"))
    )
    (net (code "83") (name "unconnected-(U201-OSC1{slash}CLKI{slash}RC12-Pad63)") (class "Default")
      (node (ref "U201") (pin "63") (pinfunction "OSC1/CLKI/RC12_63") (pintype "passive"))
    )
    (net (code "84") (name "unconnected-(U201-OSC2{slash}CLKO{slash}RC15-Pad64)") (class "Default")
      (node (ref "U201") (pin "64") (pinfunction "OSC2/CLKO/RC15_64") (pintype "passive"))
    )
    (net (code "85") (name "unconnected-(U201-PMD12{slash}IC5{slash}RD12-Pad79)") (class "Default")
      (node (ref "U201") (pin "79") (pinfunction "PMD12/IC5/RD12_79") (pintype "passive"))
    )
    (net (code "86") (name "unconnected-(U201-RG15-Pad1)") (class "Default")
      (node (ref "U201") (pin "1") (pinfunction "RG15_1") (pintype "passive"))
    )
    (net (code "87") (name "unconnected-(U201-SOSCI{slash}CN1{slash}RC13-Pad73)") (class "Default")
      (node (ref "U201") (pin "73") (pinfunction "SOSCI/CN1/RC13_73") (pintype "passive"))
    )
    (net (code "88") (name "unconnected-(U201-TCK{slash}RA1-Pad38)") (class "Default")
      (node (ref "U201") (pin "38") (pinfunction "TCK/RA1_38") (pintype "passive"))
    )
    (net (code "89") (name "unconnected-(U201-TDI{slash}RA4-Pad60)") (class "Default")
      (node (ref "U201") (pin "60") (pinfunction "TDI/RA4_60") (pintype "passive"))
    )
    (net (code "90") (name "unconnected-(U201-TDO{slash}RA5-Pad61)") (class "Default")
      (node (ref "U201") (pin "61") (pinfunction "TDO/RA5_61") (pintype "passive"))
    )
    (net (code "91") (name "unconnected-(U201-TMS{slash}RA0-Pad17)") (class "Default")
      (node (ref "U201") (pin "17") (pinfunction "TMS/RA0_17") (pintype "passive"))
    )
    (net (code "92") (name "unconnected-(U201-~{U1RTS}{slash}BCLK1{slash}CN21{slash}RD15-Pad48)") (class "Default")
      (node (ref "U201") (pin "48") (pinfunction "~{U1RTS}/BCLK1/CN21/RD15_48") (pintype "passive"))
    )
    (net (code "93") (name "unconnected-(U201-~{U2CTS}{slash}RF12-Pad40)") (class "Default")
      (node (ref "U201") (pin "40") (pinfunction "~{U2CTS}/RF12_40") (pintype "passive"))
    )
    (net (code "94") (name "unconnected-(U201-~{U2RTS}{slash}BCLK2{slash}RF13-Pad39)") (class "Default")
      (node (ref "U201") (pin "39") (pinfunction "~{U2RTS}/BCLK2/RF13_39") (pintype "passive"))
    )
    (net (code "95") (name "unconnected-(U202-NC-Pad1)") (class "Default")
      (node (ref "U202") (pin "1") (pinfunction "NC_1") (pintype "passive"))
    )
    (net (code "96") (name "unconnected-(U202-NC-Pad2)") (class "Default")
      (node (ref "U202") (pin "2") (pinfunction "NC_2") (pintype "passive"))
    )
    (net (code "97") (name "unconnected-(U202-NC-Pad3)") (class "Default")
      (node (ref "U202") (pin "3") (pinfunction "NC_3") (pintype "passive"))
    )
  )
)
